# S06.net
KiCad netlist of a schematic drawn in Altium Designer
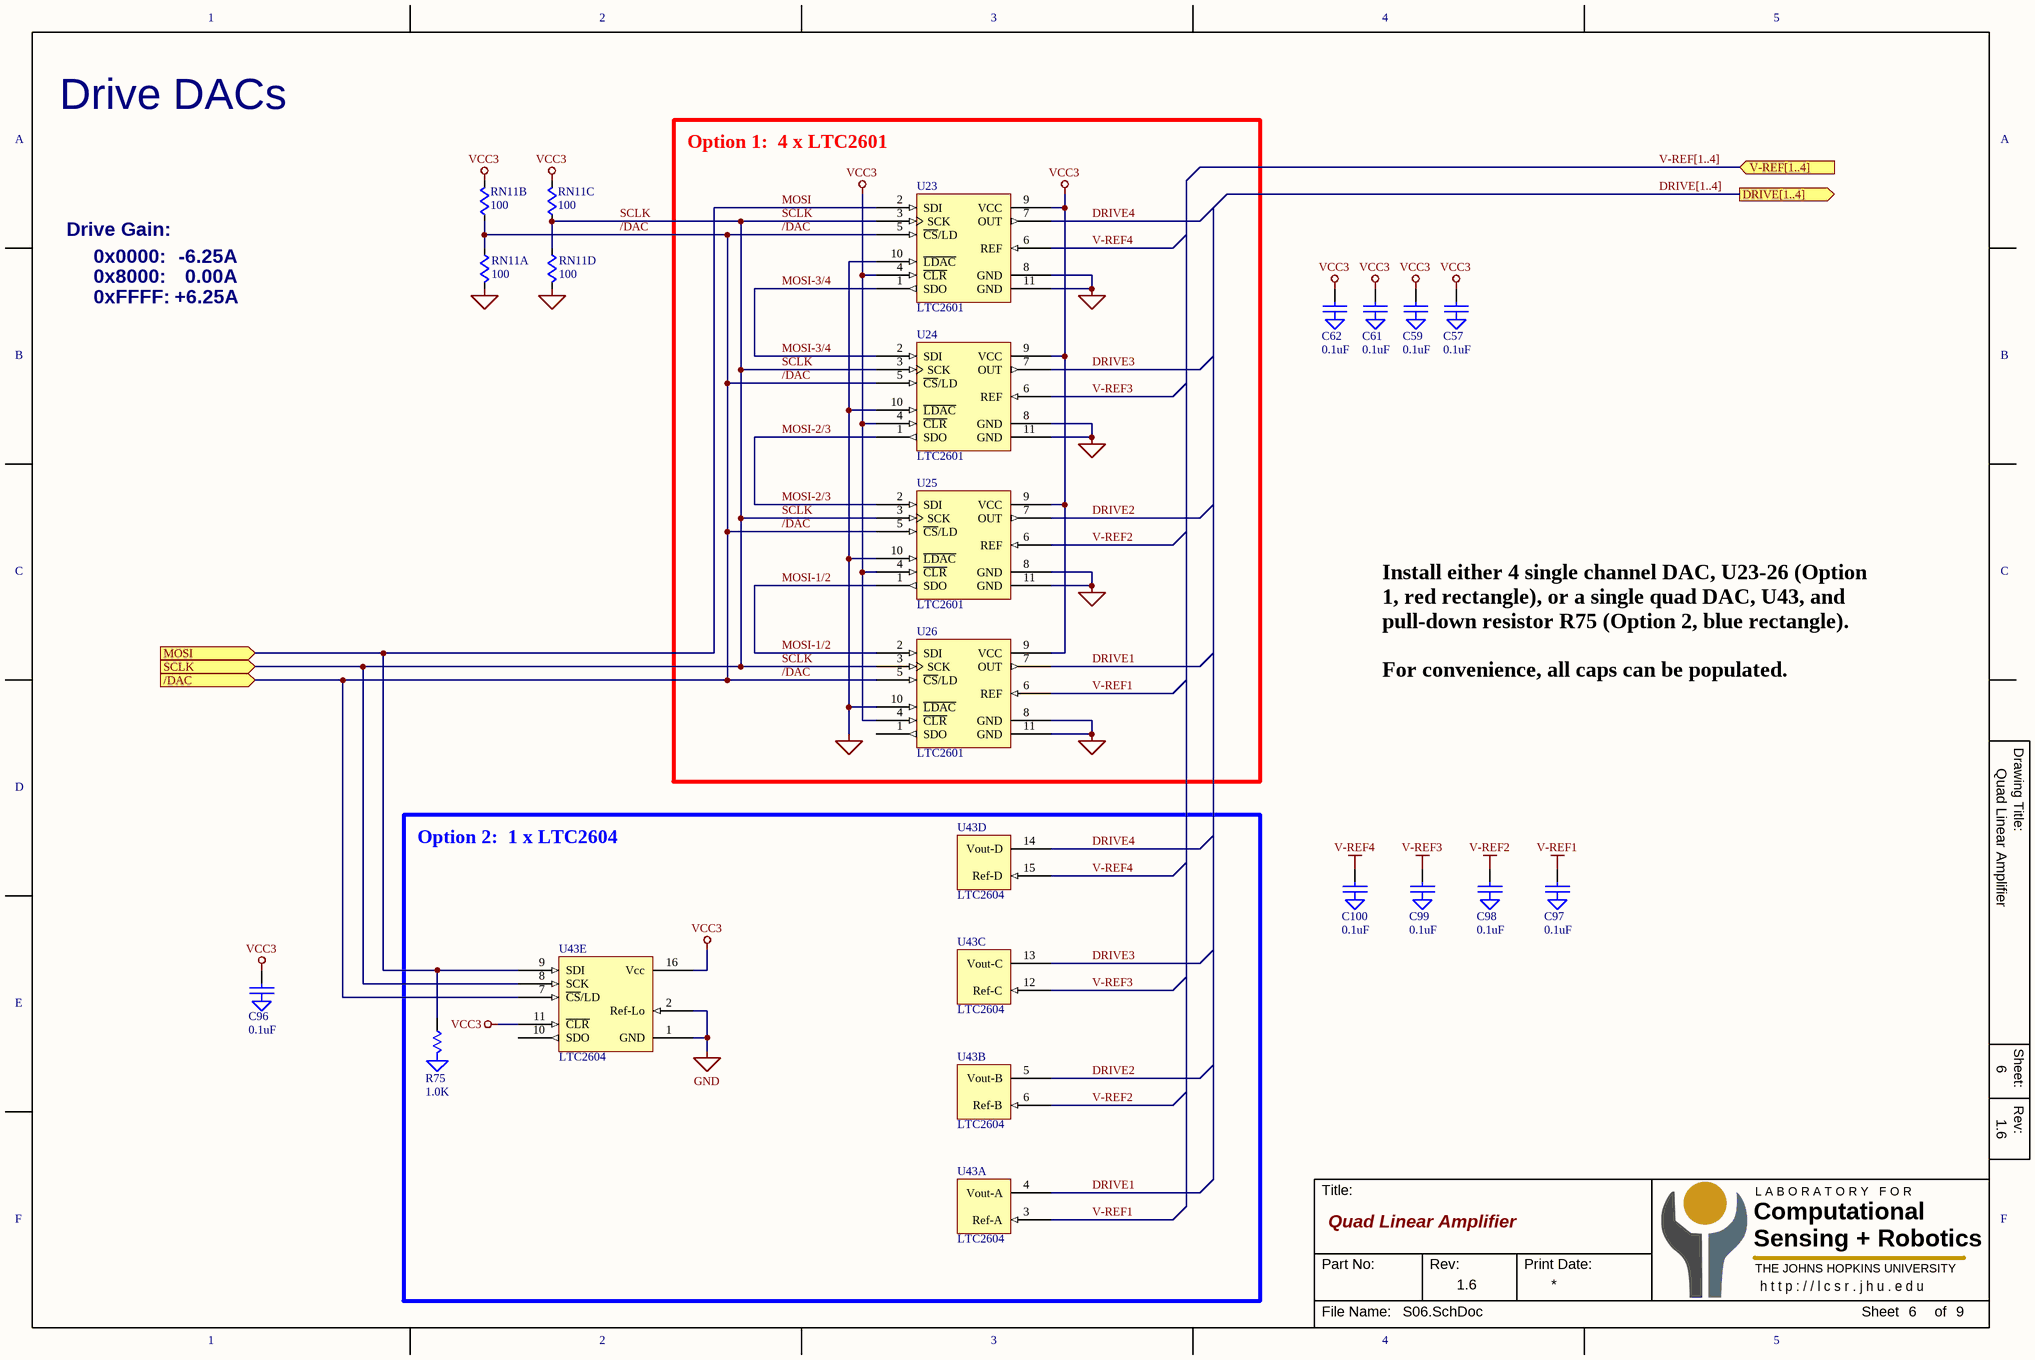
[diagram p0: S06.SchDoc]

(export (version "E")
  (design (tool "Eeschema 10.0.6"))
  (components
    (comp (ref "C57") (value "0.1uF") (footprint "C0603") (libsource (lib "") (part "CAP-GND_1")))
    (comp (ref "C59") (value "0.1uF") (footprint "C0603") (libsource (lib "") (part "CAP-GND_1")))
    (comp (ref "C61") (value "0.1uF") (footprint "C0603") (libsource (lib "") (part "CAP-GND_1")))
    (comp (ref "C62") (value "0.1uF") (footprint "C0603") (libsource (lib "") (part "CAP-GND_1")))
    (comp (ref "C96") (value "0.1uF") (footprint "C0603") (libsource (lib "QLA") (part "CAP-GND")))
    (comp (ref "C97") (value "0.1uF") (footprint "C0603") (libsource (lib "QLA") (part "CAP-GND")))
    (comp (ref "C98") (value "0.1uF") (footprint "C0603") (libsource (lib "QLA") (part "CAP-GND")))
    (comp (ref "C99") (value "0.1uF") (footprint "C0603") (libsource (lib "QLA") (part "CAP-GND")))
    (comp (ref "C100") (value "0.1uF") (footprint "C0603") (libsource (lib "QLA") (part "CAP-GND")))
    (comp (ref "R75") (value "1.0K") (footprint "R0603") (libsource (lib "QLA") (part "R-GND")))
    (comp (ref "RN11") (value "100") (footprint "RN-742C083") (libsource (lib "QLA") (part "RN-DISC-SM-4X")))
    (comp (ref "U23") (value "LTC2601") (footprint "DFN-10") (libsource (lib "QLA") (part "LTC2601")))
    (comp (ref "U24") (value "LTC2601") (footprint "DFN-10") (libsource (lib "QLA") (part "LTC2601")))
    (comp (ref "U25") (value "LTC2601") (footprint "DFN-10") (libsource (lib "QLA") (part "LTC2601")))
    (comp (ref "U26") (value "LTC2601") (footprint "DFN-10") (libsource (lib "QLA") (part "LTC2601")))
    (comp (ref "U43") (value "LTC2604") (footprint "QSOP-16") (libsource (lib "QLA") (part "LTC2604")))
  )
  (nets
    (net (code "1") (name "/DRIVE1") (class "Default")
      (node (ref "U26") (pin "7") (pinfunction "OUT_7") (pintype "output"))
      (node (ref "U43") (pin "4") (pinfunction "Vout-A_4") (pintype "passive"))
    )
    (net (code "2") (name "/DRIVE2") (class "Default")
      (node (ref "U25") (pin "7") (pinfunction "OUT_7") (pintype "output"))
      (node (ref "U43") (pin "5") (pinfunction "Vout-B_5") (pintype "passive"))
    )
    (net (code "3") (name "/DRIVE3") (class "Default")
      (node (ref "U24") (pin "7") (pinfunction "OUT_7") (pintype "output"))
      (node (ref "U43") (pin "13") (pinfunction "Vout-C_13") (pintype "passive"))
    )
    (net (code "4") (name "/DRIVE4") (class "Default")
      (node (ref "U23") (pin "7") (pinfunction "OUT_7") (pintype "output"))
      (node (ref "U43") (pin "14") (pinfunction "Vout-D_14") (pintype "passive"))
    )
    (net (code "6") (name "/MOSI") (class "Default")
      (node (ref "R75") (pin "1") (pinfunction "1_1") (pintype "passive"))
      (node (ref "U23") (pin "2") (pinfunction "SDI_2") (pintype "input"))
      (node (ref "U43") (pin "9") (pinfunction "SDI_9") (pintype "input"))
    )
    (net (code "7") (name "/MOSI-1{slash}2") (class "Default")
      (node (ref "U25") (pin "1") (pinfunction "SDO_1") (pintype "output"))
      (node (ref "U26") (pin "2") (pinfunction "SDI_2") (pintype "input"))
    )
    (net (code "8") (name "/MOSI-2{slash}3") (class "Default")
      (node (ref "U24") (pin "1") (pinfunction "SDO_1") (pintype "output"))
      (node (ref "U25") (pin "2") (pinfunction "SDI_2") (pintype "input"))
    )
    (net (code "9") (name "/MOSI-3{slash}4") (class "Default")
      (node (ref "U23") (pin "1") (pinfunction "SDO_1") (pintype "output"))
      (node (ref "U24") (pin "2") (pinfunction "SDI_2") (pintype "input"))
    )
    (net (code "10") (name "/SCLK") (class "Default")
      (node (ref "RN11") (pin "3") (pinfunction "3_3") (pintype "passive"))
      (node (ref "RN11") (pin "4") (pinfunction "4_4") (pintype "passive"))
      (node (ref "U23") (pin "3") (pinfunction "SCK_3") (pintype "input"))
      (node (ref "U24") (pin "3") (pinfunction "SCK_3") (pintype "input"))
      (node (ref "U25") (pin "3") (pinfunction "SCK_3") (pintype "input"))
      (node (ref "U26") (pin "3") (pinfunction "SCK_3") (pintype "input"))
      (node (ref "U43") (pin "8") (pinfunction "SCK_8") (pintype "input"))
    )
    (net (code "12") (name "/{slash}DAC") (class "Default")
      (node (ref "RN11") (pin "1") (pinfunction "1_1") (pintype "passive"))
      (node (ref "RN11") (pin "2") (pinfunction "2_2") (pintype "passive"))
      (node (ref "U23") (pin "5") (pinfunction "~{CS}/LD_5") (pintype "input"))
      (node (ref "U24") (pin "5") (pinfunction "~{CS}/LD_5") (pintype "input"))
      (node (ref "U25") (pin "5") (pinfunction "~{CS}/LD_5") (pintype "input"))
      (node (ref "U26") (pin "5") (pinfunction "~{CS}/LD_5") (pintype "input"))
      (node (ref "U43") (pin "7") (pinfunction "~{CS}/LD_7") (pintype "input"))
    )
    (net (code "13") (name "GND") (class "Default")
      (node (ref "C100") (pin "2") (pinfunction "GND_2") (pintype "power_in"))
      (node (ref "C57") (pin "2") (pinfunction "GND_2") (pintype "power_in"))
      (node (ref "C59") (pin "2") (pinfunction "GND_2") (pintype "power_in"))
      (node (ref "C61") (pin "2") (pinfunction "GND_2") (pintype "power_in"))
      (node (ref "C62") (pin "2") (pinfunction "GND_2") (pintype "power_in"))
      (node (ref "C96") (pin "2") (pinfunction "GND_2") (pintype "power_in"))
      (node (ref "C97") (pin "2") (pinfunction "GND_2") (pintype "power_in"))
      (node (ref "C98") (pin "2") (pinfunction "GND_2") (pintype "power_in"))
      (node (ref "C99") (pin "2") (pinfunction "GND_2") (pintype "power_in"))
      (node (ref "R75") (pin "2") (pinfunction "GND_2") (pintype "power_in"))
      (node (ref "RN11") (pin "5") (pinfunction "5_5") (pintype "passive"))
      (node (ref "RN11") (pin "8") (pinfunction "8_8") (pintype "passive"))
      (node (ref "U23") (pin "10") (pinfunction "LDAC_10") (pintype "input"))
      (node (ref "U23") (pin "11") (pinfunction "GND_11") (pintype "power_in"))
      (node (ref "U23") (pin "8") (pinfunction "GND_8") (pintype "power_in"))
      (node (ref "U24") (pin "10") (pinfunction "LDAC_10") (pintype "input"))
      (node (ref "U24") (pin "11") (pinfunction "GND_11") (pintype "power_in"))
      (node (ref "U24") (pin "8") (pinfunction "GND_8") (pintype "power_in"))
      (node (ref "U25") (pin "10") (pinfunction "LDAC_10") (pintype "input"))
      (node (ref "U25") (pin "11") (pinfunction "GND_11") (pintype "power_in"))
      (node (ref "U25") (pin "8") (pinfunction "GND_8") (pintype "power_in"))
      (node (ref "U26") (pin "10") (pinfunction "LDAC_10") (pintype "input"))
      (node (ref "U26") (pin "11") (pinfunction "GND_11") (pintype "power_in"))
      (node (ref "U26") (pin "8") (pinfunction "GND_8") (pintype "power_in"))
      (node (ref "U43") (pin "1") (pinfunction "GND_1") (pintype "power_in"))
      (node (ref "U43") (pin "2") (pinfunction "Ref-Lo_2") (pintype "input"))
    )
    (net (code "14") (name "V-REF1") (class "Default")
      (node (ref "C97") (pin "1") (pintype "passive"))
      (node (ref "U26") (pin "6") (pinfunction "REF_6") (pintype "input"))
      (node (ref "U43") (pin "3") (pinfunction "Ref-A_3") (pintype "input"))
    )
    (net (code "15") (name "V-REF2") (class "Default")
      (node (ref "C98") (pin "1") (pintype "passive"))
      (node (ref "U25") (pin "6") (pinfunction "REF_6") (pintype "input"))
      (node (ref "U43") (pin "6") (pinfunction "Ref-B_6") (pintype "input"))
    )
    (net (code "16") (name "V-REF3") (class "Default")
      (node (ref "C99") (pin "1") (pintype "passive"))
      (node (ref "U24") (pin "6") (pinfunction "REF_6") (pintype "input"))
      (node (ref "U43") (pin "12") (pinfunction "Ref-C_12") (pintype "input"))
    )
    (net (code "17") (name "V-REF4") (class "Default")
      (node (ref "C100") (pin "1") (pintype "passive"))
      (node (ref "U23") (pin "6") (pinfunction "REF_6") (pintype "input"))
      (node (ref "U43") (pin "15") (pinfunction "Ref-D_15") (pintype "input"))
    )
    (net (code "18") (name "VCC3") (class "Default")
      (node (ref "C57") (pin "1") (pintype "passive"))
      (node (ref "C59") (pin "1") (pintype "passive"))
      (node (ref "C61") (pin "1") (pintype "passive"))
      (node (ref "C62") (pin "1") (pintype "passive"))
      (node (ref "C96") (pin "1") (pintype "passive"))
      (node (ref "RN11") (pin "6") (pinfunction "6_6") (pintype "passive"))
      (node (ref "RN11") (pin "7") (pinfunction "7_7") (pintype "passive"))
      (node (ref "U23") (pin "4") (pinfunction "CLR_4") (pintype "input"))
      (node (ref "U23") (pin "9") (pinfunction "VCC_9") (pintype "power_in"))
      (node (ref "U24") (pin "4") (pinfunction "CLR_4") (pintype "input"))
      (node (ref "U24") (pin "9") (pinfunction "VCC_9") (pintype "power_in"))
      (node (ref "U25") (pin "4") (pinfunction "CLR_4") (pintype "input"))
      (node (ref "U25") (pin "9") (pinfunction "VCC_9") (pintype "power_in"))
      (node (ref "U26") (pin "4") (pinfunction "CLR_4") (pintype "input"))
      (node (ref "U26") (pin "9") (pinfunction "VCC_9") (pintype "power_in"))
      (node (ref "U43") (pin "11") (pinfunction "~{CLR}_11") (pintype "input"))
      (node (ref "U43") (pin "16") (pinfunction "Vcc_16") (pintype "power_in"))
    )
    (net (code "19") (name "unconnected-(U26-SDO-Pad1)") (class "Default")
      (node (ref "U26") (pin "1") (pinfunction "SDO_1") (pintype "output"))
    )
    (net (code "20") (name "unconnected-(U43E-SDO-Pad10)") (class "Default")
      (node (ref "U43") (pin "10") (pinfunction "SDO_10") (pintype "output"))
    )
  )
)
